# Voltage_Source.net
KiCad netlist of a schematic drawn in Altium Designer
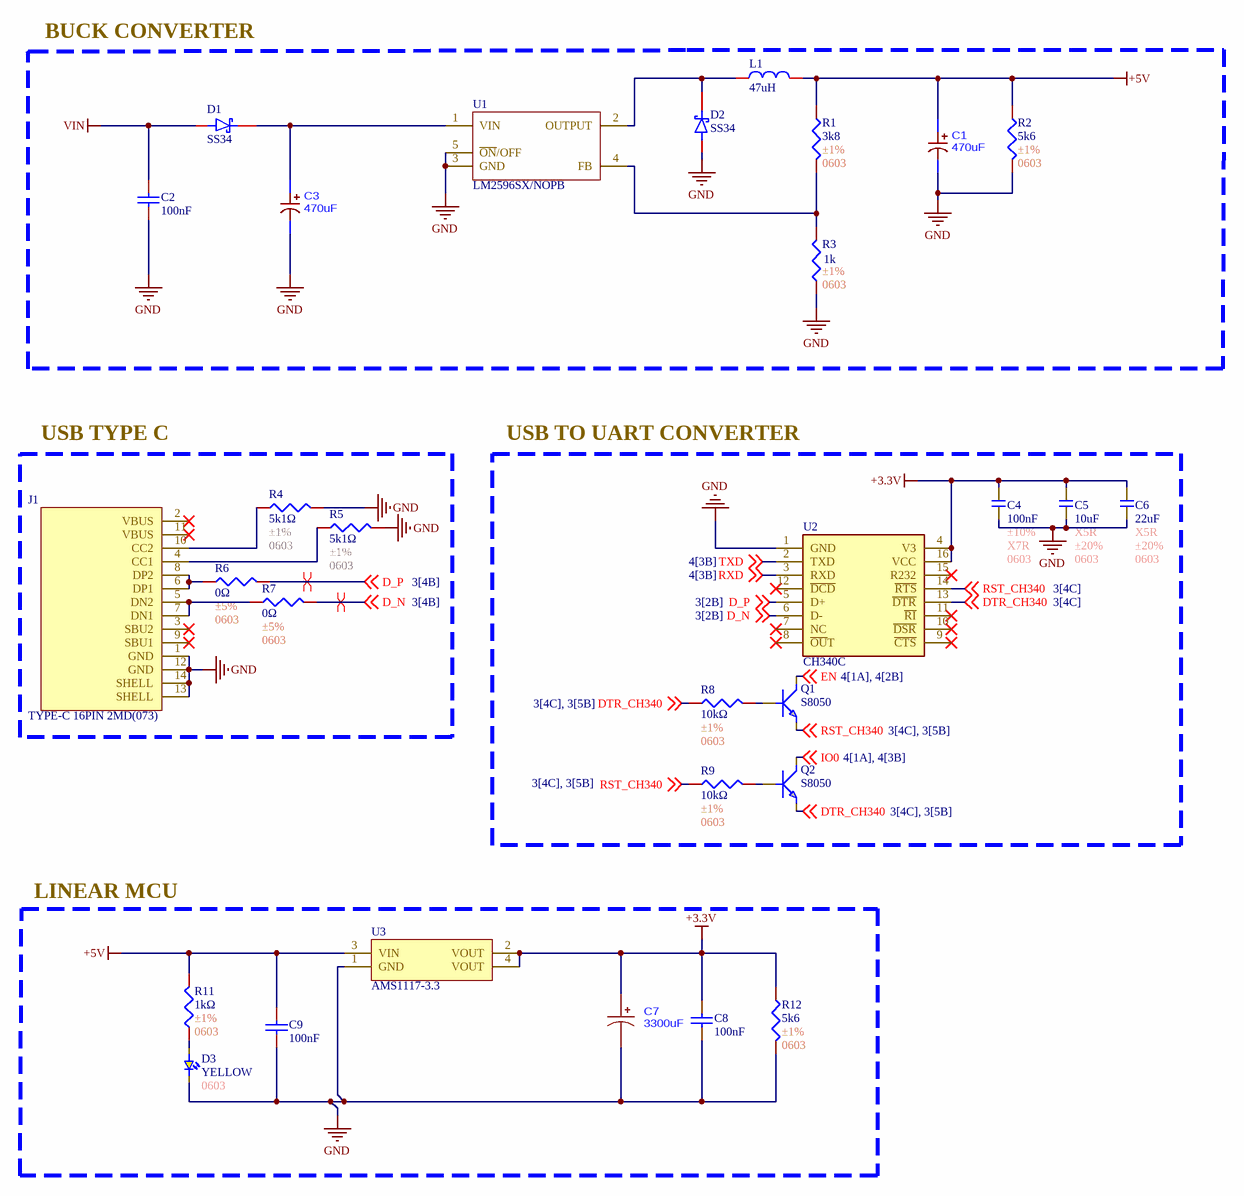
[diagram p0: Voltage Source.SchDoc]

(export (version "E")
  (design (tool "Eeschema 10.0.6"))
  (components
    (comp (ref "C1")
      (value "470uF")
      (footprint "470uF 35V, D10xL13mm")
      (description "470uF ±20% 35V Through Hole,D10xL13mm")
      (fields (field (name "MANUFACTURER") "AISHI") (field (name "MFR. PART #") "SPZ1VM471G13O00RAXXX"))
      (libsource (lib "Capital") (part "470uF  35V, D10xL13mm"))
    )
    (comp (ref "C2")
      (value "100nF")
      (footprint "tu tantalum dip5.08")
      (description "Cắm")
      (libsource (lib "Capital") (part "Tu tantalum 100nF 50V 20% DIP5.08"))
    )
    (comp (ref "C3")
      (value "470uF")
      (footprint "470uF 35V, D10xL13mm")
      (description "470uF ±20% 35V Through Hole,D10xL13mm")
      (fields (field (name "MANUFACTURER") "AISHI") (field (name "MFR. PART #") "SPZ1VM471G13O00RAXXX"))
      (libsource (lib "Capital") (part "470uF  35V, D10xL13mm"))
    )
    (comp (ref "C4")
      (value "100nF")
      (footprint "C0603")
      (description "50V 100nF X7R ±10% 0603 Multilayer Ceramic Capacitors MLCC - SMD/SMT ROHS")
      (fields
        (field (name "MANUFACTURER") "YAGEO")
        (field (name "MFR. PART #") "CC0603KRX7R9BB104")
        (field (name "TOLERANCE") "±10%")
        (field (name "TEMPERATURE COEFFICIENT") "X7R")
        (field (name "PACKAGE") "0603")
      )
      (libsource (lib "DSP_VERSION_1.0") (part "C0603_100nF_±10%_X7R"))
    )
    (comp (ref "C5")
      (value "10uF")
      (footprint "C0603")
      (description "25V 10uF X5R ±20% 0603 Multilayer Ceramic Capacitors MLCC - SMD/SMT ROHS")
      (fields
        (field (name "MANUFACTURER") "YAGEO")
        (field (name "MFR. PART #") "CC0603MRX5R8BB106")
        (field (name "TEMPERATURE COEFFICIENT") "X5R")
        (field (name "TOLERANCE") "±20%")
        (field (name "PACKAGE") "0603")
      )
      (libsource (lib "DSP_VERSION_1.0") (part "C0603_10uF_±10%_X7R"))
    )
    (comp (ref "C6")
      (value "22uF")
      (footprint "C0603")
      (description "6.3V 22uF X5R ±20% 0603 Multilayer Ceramic Capacitors MLCC - SMD/SMT ROHS")
      (fields
        (field (name "MANUFACTURER") "YAGEO")
        (field (name "MFR. PART #") "CC0603MRX5R5BB226")
        (field (name "TEMPERATURE COEFFICIENT") "X5R")
        (field (name "TOLERANCE") "±20%")
        (field (name "PACKAGE") "0603")
      )
      (libsource (lib "DSP_VERSION_1.0") (part "C0603_22uF_±20%_X5R"))
    )
    (comp (ref "C7")
      (value "3300uF")
      (footprint "Through Hole,D8xL16mm")
      (description "3300uF ±20% 6.3V Through Hole,D8xL16mm 2000hrs")
      (fields (field (name "MANUFACTURER") "Honor Elec") (field (name "MFR. PART #") "HS0J338M0816PC"))
      (libsource (lib "Capital") (part "Through Hole,D8xL16mm"))
    )
    (comp (ref "C8")
      (value "100nF")
      (footprint "tu tantalum dip5.08")
      (description "Cắm")
      (libsource (lib "Capital") (part "Tu tantalum 100nF 50V 20% DIP5.08"))
    )
    (comp (ref "C9")
      (value "100nF")
      (footprint "tu tantalum dip5.08")
      (description "Cắm")
      (libsource (lib "Capital") (part "Tu tantalum 100nF 50V 20% DIP5.08"))
    )
    (comp (ref "D1")
      (value "SS34")
      (footprint "SS34")
      (description "40V Independent 3A 550mV@3A SMA(DO-214AC) Schottky Diodes ROHS")
      (fields
        (field (name "MANUFACTURER") "MDD(Microdiode Semiconductor)")
        (field (name "LCSC PART #") "C8678")
      )
      (libsource (lib "Diode") (part "SS34"))
    )
    (comp (ref "D2")
      (value "SS34")
      (footprint "SS34")
      (description "40V Independent 3A 550mV@3A SMA(DO-214AC) Schottky Diodes ROHS")
      (fields
        (field (name "MANUFACTURER") "MDD(Microdiode Semiconductor)")
        (field (name "LCSC PART #") "C8678")
      )
      (libsource (lib "Diode") (part "SS34"))
    )
    (comp (ref "D3")
      (value "YELLOW")
      (footprint "LED0603")
      (description "25mcd~40mcd Water Clear -40℃~+85℃ 624nm Red 120° 60mW 0402 LED Indication - Discrete ROHS")
      (fields
        (field (name "MANUFACTURER") "XINGLIGHT")
        (field (name "MFR. PART #") "XL-1005UGC")
        (field (name "PACKAGE") "0603")
      )
      (libsource (lib "LED") (part "D0603_YELLOW"))
    )
    (comp (ref "J1")
      (value "TYPE-C 16PIN 2MD(073)")
      (footprint "TYPE_C_FAMALE")
      (description "3A 1 Surface Mount, Right Angle 16P Female -25℃~+85℃ Type-C SMD USB Connectors ROHS")
      (fields (field (name "MANUFACTURER") "SHOU HAN") (field (name "LCSC PART #") "C2765186"))
      (libsource (lib "Connector") (part "TYPE_C_FAMALE_16PIN"))
    )
    (comp (ref "L1")
      (value "47uH")
      (footprint "CD43")
      (description "1.15A 10uH Unshielded Inductor ±20% SMD,4x4.5mm Power Inductors ROHS")
      (fields (field (name "MANUFACTURER") "ZE") (field (name "MFR. PART #") "CD43-100M"))
      (libsource (lib "Inductor") (part "CD4-10UH"))
    )
    (comp (ref "Q1")
      (value "S8050")
      (footprint "S8050")
      (description "25V 300mW 500mA SOT-23 Bipolar (BJT) ROHS")
      (fields (field (name "MANUFACTURER") "JSMSEMI") (field (name "LCSC PART #") "C916390"))
      (libsource (lib "Transistor") (part "S8050"))
    )
    (comp (ref "Q2")
      (value "S8050")
      (footprint "S8050")
      (description "25V 300mW 500mA SOT-23 Bipolar (BJT) ROHS")
      (fields (field (name "MANUFACTURER") "JSMSEMI") (field (name "LCSC PART #") "C916390"))
      (libsource (lib "Transistor") (part "S8050"))
    )
    (comp (ref "R1")
      (value "3k8")
      (footprint "R0603")
      (description "62.5mW Thick Film Resistor 50V ±1% ±200ppm/℃ 10Ω 0402 Chip Resistor - Surface Mount ROHS")
      (fields
        (field (name "MANUFACTURER") "YAGEO")
        (field (name "MFR. PART #") "RC0402FR-0710RL")
        (field (name "TOLERANCE") "±1%")
        (field (name "PACKAGE") "0603")
      )
      (libsource (lib "Resistor") (part "R0603_4k7Ω_±1%"))
    )
    (comp (ref "R2")
      (value "5k6")
      (footprint "R0603")
      (description "62.5mW Thick Film Resistor 50V ±1% ±200ppm/℃ 10Ω 0402 Chip Resistor - Surface Mount ROHS")
      (fields
        (field (name "MANUFACTURER") "YAGEO")
        (field (name "MFR. PART #") "RC0402FR-0710RL")
        (field (name "TOLERANCE") "±1%")
        (field (name "PACKAGE") "0603")
      )
      (libsource (lib "Resistor") (part "R0603_4k7Ω_±1%"))
    )
    (comp (ref "R3")
      (value "1k")
      (footprint "R0603")
      (description "62.5mW Thick Film Resistor 50V ±1% ±200ppm/℃ 10Ω 0402 Chip Resistor - Surface Mount ROHS")
      (fields
        (field (name "MANUFACTURER") "YAGEO")
        (field (name "MFR. PART #") "RC0402FR-0710RL")
        (field (name "TOLERANCE") "±1%")
        (field (name "PACKAGE") "0603")
      )
      (libsource (lib "Resistor") (part "R0603_4k7Ω_±1%"))
    )
    (comp (ref "R4")
      (value "5k1Ω")
      (footprint "R0603")
      (description "100mW Thick Film Resistor 75V ±100ppm/℃ ±1% 5.1kΩ 0603 Chip Resistor - Surface Mount ROHS")
      (fields
        (field (name "MANUFACTURER") "FOJAN")
        (field (name "MFR. PART #") "FRC0603F5101TS")
        (field (name "TOLERANCE") "±1%")
        (field (name "PACKAGE") "0603")
      )
      (libsource (lib "Resistor") (part "R0603_5k1Ω_±1%"))
    )
    (comp (ref "R5")
      (value "5k1Ω")
      (footprint "R0603")
      (description "100mW Thick Film Resistor 75V ±100ppm/℃ ±1% 5.1kΩ 0603 Chip Resistor - Surface Mount ROHS")
      (fields
        (field (name "MANUFACTURER") "FOJAN")
        (field (name "MFR. PART #") "FRC0603F5101TS")
        (field (name "TOLERANCE") "±1%")
        (field (name "PACKAGE") "0603")
      )
      (libsource (lib "Resistor") (part "R0603_5k1Ω_±1%"))
    )
    (comp (ref "R6")
      (value "0Ω")
      (footprint "R0603")
      (description "100mW Thick Film Resistor 75V ±5% 0Ω 0603 Chip Resistor - Surface Mount ROHS")
      (fields
        (field (name "MANUFACTURER") "YAGEO")
        (field (name "MFR. PART #") "RC0603JR-070RL")
        (field (name "TOLERANCE") "±5%")
        (field (name "PACKAGE") "0603")
      )
      (libsource (lib "Resistor") (part "R0603_0Ω_±5%"))
    )
    (comp (ref "R7")
      (value "0Ω")
      (footprint "R0603")
      (description "100mW Thick Film Resistor 75V ±5% 0Ω 0603 Chip Resistor - Surface Mount ROHS")
      (fields
        (field (name "MANUFACTURER") "YAGEO")
        (field (name "MFR. PART #") "RC0603JR-070RL")
        (field (name "TOLERANCE") "±5%")
        (field (name "PACKAGE") "0603")
      )
      (libsource (lib "Resistor") (part "R0603_0Ω_±5%"))
    )
    (comp (ref "R8")
      (value "10kΩ")
      (footprint "R0603")
      (description "62.5mW Thick Film Resistor 50V ±1% ±200ppm/℃ 10Ω 0402 Chip Resistor - Surface Mount ROHS")
      (fields
        (field (name "MANUFACTURER") "YAGEO")
        (field (name "MFR. PART #") "RC0402FR-0710RL")
        (field (name "TOLERANCE") "±1%")
        (field (name "PACKAGE") "0603")
      )
      (libsource (lib "Resistor") (part "R0603_10kΩ_±1%"))
    )
    (comp (ref "R9")
      (value "10kΩ")
      (footprint "R0603")
      (description "62.5mW Thick Film Resistor 50V ±1% ±200ppm/℃ 10Ω 0402 Chip Resistor - Surface Mount ROHS")
      (fields
        (field (name "MANUFACTURER") "YAGEO")
        (field (name "MFR. PART #") "RC0402FR-0710RL")
        (field (name "TOLERANCE") "±1%")
        (field (name "PACKAGE") "0603")
      )
      (libsource (lib "Resistor") (part "R0603_10kΩ_±1%"))
    )
    (comp (ref "R11")
      (value "1kΩ")
      (footprint "R0603")
      (description "62.5mW Thick Film Resistor 50V ±1% ±200ppm/℃ 10Ω 0402 Chip Resistor - Surface Mount ROHS")
      (fields
        (field (name "MANUFACTURER") "YAGEO")
        (field (name "MFR. PART #") "RC0402FR-0710RL")
        (field (name "TOLERANCE") "±1%")
        (field (name "PACKAGE") "0603")
      )
      (libsource (lib "Resistor") (part "R0603_1kΩ_±1%"))
    )
    (comp (ref "R12")
      (value "5k6")
      (footprint "R0603")
      (description "62.5mW Thick Film Resistor 50V ±1% ±200ppm/℃ 10Ω 0402 Chip Resistor - Surface Mount ROHS")
      (fields
        (field (name "MANUFACTURER") "YAGEO")
        (field (name "MFR. PART #") "RC0402FR-0710RL")
        (field (name "TOLERANCE") "±1%")
        (field (name "PACKAGE") "0603")
      )
      (libsource (lib "Resistor") (part "R0603_4k7Ω_±1%"))
    )
    (comp (ref "U1")
      (value "LM2596SX/NOPB")
      (footprint "LM2596SX-5.0/NOPB")
      (description "150kHz Buck Fixed 1 TO-263-5 Voltage Regulators - DC DC Switching Regulators RoHS")
      (fields (field (name "MANUFACTURER") "TI") (field (name "LCSC PART #") "C10002"))
      (libsource (lib "IC") (part "LM2596SX/NOPB"))
    )
    (comp (ref "U2")
      (value "CH340C")
      (footprint "CH340C")
      (description "2Mbps Transceiver USB 2.0 SOP-16 USB Converters ROHS")
      (fields (field (name "MANUFACTURER") "WCH") (field (name "LCSC PART #") "C84681"))
      (libsource (lib "IC") (part "CH340C"))
    )
    (comp (ref "U3")
      (value "AMS1117-3.3")
      (footprint "AMS1117-3.3")
      (fields
        (field (name "MANUFACTURER") "Advanced Monolithic Systems")
        (field (name "LCSC PART #") "C6186")
      )
      (libsource (lib "IC") (part "AMS1117-3.3"))
    )
  )
  (nets
    (net (code "1") (name "+3.3V") (class "Default")
      (node (ref "C4") (pin "2") (pinfunction "2_2") (pintype "passive"))
      (node (ref "C5") (pin "2") (pinfunction "2_2") (pintype "passive"))
      (node (ref "C6") (pin "2") (pinfunction "2_2") (pintype "passive"))
      (node (ref "C7") (pin "1") (pinfunction "1_1") (pintype "passive"))
      (node (ref "C8") (pin "2") (pinfunction "2_2") (pintype "passive"))
      (node (ref "R12") (pin "1") (pinfunction "1_1") (pintype "passive"))
      (node (ref "U2") (pin "16") (pinfunction "VCC_16") (pintype "passive"))
      (node (ref "U2") (pin "4") (pinfunction "V3_4") (pintype "passive"))
      (node (ref "U3") (pin "2") (pinfunction "VOUT_2") (pintype "passive"))
      (node (ref "U3") (pin "4") (pinfunction "VOUT_4") (pintype "passive"))
    )
    (net (code "2") (name "+5V") (class "Default")
      (node (ref "C1") (pin "1") (pinfunction "1_1") (pintype "passive"))
      (node (ref "C9") (pin "2") (pinfunction "2_2") (pintype "passive"))
      (node (ref "L1") (pin "2") (pinfunction "2_2") (pintype "passive"))
      (node (ref "R1") (pin "1") (pinfunction "1_1") (pintype "passive"))
      (node (ref "R11") (pin "2") (pinfunction "2_2") (pintype "passive"))
      (node (ref "R2") (pin "1") (pinfunction "1_1") (pintype "passive"))
      (node (ref "U3") (pin "3") (pinfunction "VIN_3") (pintype "passive"))
    )
    (net (code "3") (name "DTR_CH340") (class "Default")
      (node (ref "Q2") (pin "2") (pinfunction "E_2") (pintype "passive"))
      (node (ref "R8") (pin "1") (pinfunction "1_1") (pintype "passive"))
      (node (ref "U2") (pin "13") (pinfunction "~{DTR}_13") (pintype "passive"))
    )
    (net (code "4") (name "D_N") (class "Default")
      (node (ref "R7") (pin "2") (pinfunction "2_2") (pintype "passive"))
      (node (ref "U2") (pin "6") (pinfunction "D-_6") (pintype "passive"))
    )
    (net (code "5") (name "D_P") (class "Default")
      (node (ref "R6") (pin "2") (pinfunction "2_2") (pintype "passive"))
      (node (ref "U2") (pin "5") (pinfunction "D+_5") (pintype "passive"))
    )
    (net (code "6") (name "EN") (class "Default")
      (node (ref "Q1") (pin "3") (pinfunction "C_3") (pintype "passive"))
    )
    (net (code "7") (name "GND") (class "Default")
      (node (ref "C1") (pin "2") (pinfunction "2_2") (pintype "passive"))
      (node (ref "C2") (pin "1") (pinfunction "1_1") (pintype "passive"))
      (node (ref "C3") (pin "2") (pinfunction "2_2") (pintype "passive"))
      (node (ref "C4") (pin "1") (pinfunction "1_1") (pintype "passive"))
      (node (ref "C5") (pin "1") (pinfunction "1_1") (pintype "passive"))
      (node (ref "C6") (pin "1") (pinfunction "1_1") (pintype "passive"))
      (node (ref "C7") (pin "2") (pinfunction "2_2") (pintype "passive"))
      (node (ref "C8") (pin "1") (pinfunction "1_1") (pintype "passive"))
      (node (ref "C9") (pin "1") (pinfunction "1_1") (pintype "passive"))
      (node (ref "D2") (pin "2") (pinfunction "2_2") (pintype "passive"))
      (node (ref "D3") (pin "1") (pinfunction "1_1") (pintype "passive"))
      (node (ref "J1") (pin "1") (pinfunction "GND_1") (pintype "passive"))
      (node (ref "J1") (pin "12") (pinfunction "GND_12") (pintype "passive"))
      (node (ref "J1") (pin "13") (pinfunction "SHELL_13") (pintype "passive"))
      (node (ref "J1") (pin "14") (pinfunction "SHELL_14") (pintype "passive"))
      (node (ref "R12") (pin "2") (pinfunction "2_2") (pintype "passive"))
      (node (ref "R2") (pin "2") (pinfunction "2_2") (pintype "passive"))
      (node (ref "R3") (pin "1") (pinfunction "1_1") (pintype "passive"))
      (node (ref "R4") (pin "2") (pinfunction "2_2") (pintype "passive"))
      (node (ref "R5") (pin "2") (pinfunction "2_2") (pintype "passive"))
      (node (ref "U1") (pin "3") (pinfunction "GND_3") (pintype "passive"))
      (node (ref "U1") (pin "5") (pinfunction "~{ON}/OFF_5") (pintype "passive"))
      (node (ref "U2") (pin "1") (pinfunction "GND_1") (pintype "passive"))
      (node (ref "U3") (pin "1") (pinfunction "GND_1") (pintype "passive"))
    )
    (net (code "8") (name "IO0") (class "Default")
      (node (ref "Q2") (pin "3") (pinfunction "C_3") (pintype "passive"))
    )
    (net (code "9") (name "Net-(D3-Pad2)") (class "Default")
      (node (ref "D3") (pin "2") (pinfunction "2_2") (pintype "passive"))
      (node (ref "R11") (pin "1") (pinfunction "1_1") (pintype "passive"))
    )
    (net (code "10") (name "Net-(J1-CC1)") (class "Default")
      (node (ref "J1") (pin "4") (pinfunction "CC1_4") (pintype "passive"))
      (node (ref "R5") (pin "1") (pinfunction "1_1") (pintype "passive"))
    )
    (net (code "11") (name "Net-(J1-CC2)") (class "Default")
      (node (ref "J1") (pin "10") (pinfunction "CC2_10") (pintype "passive"))
      (node (ref "R4") (pin "1") (pinfunction "1_1") (pintype "passive"))
    )
    (net (code "12") (name "Net-(J1-DN1)") (class "Default")
      (node (ref "J1") (pin "5") (pinfunction "DN2_5") (pintype "passive"))
      (node (ref "J1") (pin "7") (pinfunction "DN1_7") (pintype "passive"))
      (node (ref "R7") (pin "1") (pinfunction "1_1") (pintype "passive"))
    )
    (net (code "13") (name "Net-(J1-DP1)") (class "Default")
      (node (ref "J1") (pin "6") (pinfunction "DP1_6") (pintype "passive"))
      (node (ref "J1") (pin "8") (pinfunction "DP2_8") (pintype "passive"))
      (node (ref "R6") (pin "1") (pinfunction "1_1") (pintype "passive"))
    )
    (net (code "14") (name "Net-(Q1-B)") (class "Default")
      (node (ref "Q1") (pin "1") (pinfunction "B_1") (pintype "passive"))
      (node (ref "R8") (pin "2") (pinfunction "2_2") (pintype "passive"))
    )
    (net (code "15") (name "Net-(Q2-B)") (class "Default")
      (node (ref "Q2") (pin "1") (pinfunction "B_1") (pintype "passive"))
      (node (ref "R9") (pin "2") (pinfunction "2_2") (pintype "passive"))
    )
    (net (code "16") (name "Net-(U1-FB)") (class "Default")
      (node (ref "R1") (pin "2") (pinfunction "2_2") (pintype "passive"))
      (node (ref "R3") (pin "2") (pinfunction "2_2") (pintype "passive"))
      (node (ref "U1") (pin "4") (pinfunction "FB_4") (pintype "passive"))
    )
    (net (code "17") (name "Net-(U1-OUTPUT)") (class "Default")
      (node (ref "D2") (pin "1") (pinfunction "1_1") (pintype "passive"))
      (node (ref "L1") (pin "1") (pinfunction "1_1") (pintype "passive"))
      (node (ref "U1") (pin "2") (pinfunction "OUTPUT_2") (pintype "passive"))
    )
    (net (code "18") (name "Net-(U1-VIN)") (class "Default")
      (node (ref "C3") (pin "1") (pinfunction "1_1") (pintype "passive"))
      (node (ref "D1") (pin "1") (pinfunction "1_1") (pintype "passive"))
      (node (ref "U1") (pin "1") (pinfunction "VIN_1") (pintype "passive"))
    )
    (net (code "19") (name "RST_CH340") (class "Default")
      (node (ref "Q1") (pin "2") (pinfunction "E_2") (pintype "passive"))
      (node (ref "R9") (pin "1") (pinfunction "1_1") (pintype "passive"))
      (node (ref "U2") (pin "14") (pinfunction "~{RTS}_14") (pintype "passive"))
    )
    (net (code "20") (name "RXD") (class "Default")
      (node (ref "U2") (pin "3") (pinfunction "RXD_3") (pintype "passive"))
    )
    (net (code "21") (name "TXD") (class "Default")
      (node (ref "U2") (pin "2") (pinfunction "TXD_2") (pintype "passive"))
    )
    (net (code "22") (name "VIN") (class "Default")
      (node (ref "C2") (pin "2") (pinfunction "2_2") (pintype "passive"))
      (node (ref "D1") (pin "2") (pinfunction "2_2") (pintype "passive"))
    )
    (net (code "23") (name "unconnected-(J1-SBU1-Pad9)") (class "Default")
      (node (ref "J1") (pin "9") (pinfunction "SBU1_9") (pintype "passive+no_connect"))
    )
    (net (code "24") (name "unconnected-(J1-SBU2-Pad3)") (class "Default")
      (node (ref "J1") (pin "3") (pinfunction "SBU2_3") (pintype "passive+no_connect"))
    )
    (net (code "25") (name "unconnected-(J1-VBUS-Pad2)") (class "Default")
      (node (ref "J1") (pin "2") (pinfunction "VBUS_2") (pintype "passive+no_connect"))
    )
    (net (code "26") (name "unconnected-(J1-VBUS-Pad11)") (class "Default")
      (node (ref "J1") (pin "11") (pinfunction "VBUS_11") (pintype "passive+no_connect"))
    )
    (net (code "27") (name "unconnected-(U2-NC-Pad7)") (class "Default")
      (node (ref "U2") (pin "7") (pinfunction "NC_7") (pintype "passive+no_connect"))
    )
    (net (code "28") (name "unconnected-(U2-R232-Pad15)") (class "Default")
      (node (ref "U2") (pin "15") (pinfunction "R232_15") (pintype "passive+no_connect"))
    )
    (net (code "29") (name "unconnected-(U2-~{CTS}-Pad9)") (class "Default")
      (node (ref "U2") (pin "9") (pinfunction "~{CTS}_9") (pintype "passive+no_connect"))
    )
    (net (code "30") (name "unconnected-(U2-~{DCD}-Pad12)") (class "Default")
      (node (ref "U2") (pin "12") (pinfunction "~{DCD}_12") (pintype "passive+no_connect"))
    )
    (net (code "31") (name "unconnected-(U2-~{DSR}-Pad10)") (class "Default")
      (node (ref "U2") (pin "10") (pinfunction "~{DSR}_10") (pintype "passive+no_connect"))
    )
    (net (code "32") (name "unconnected-(U2-~{OU}T-Pad8)") (class "Default")
      (node (ref "U2") (pin "8") (pinfunction "~{OU}T_8") (pintype "passive+no_connect"))
    )
    (net (code "33") (name "unconnected-(U2-~{RI}-Pad11)") (class "Default")
      (node (ref "U2") (pin "11") (pinfunction "~{RI}_11") (pintype "passive+no_connect"))
    )
  )
)
